# usbasp.net
KiCad netlist of a schematic drawn in EAGLE
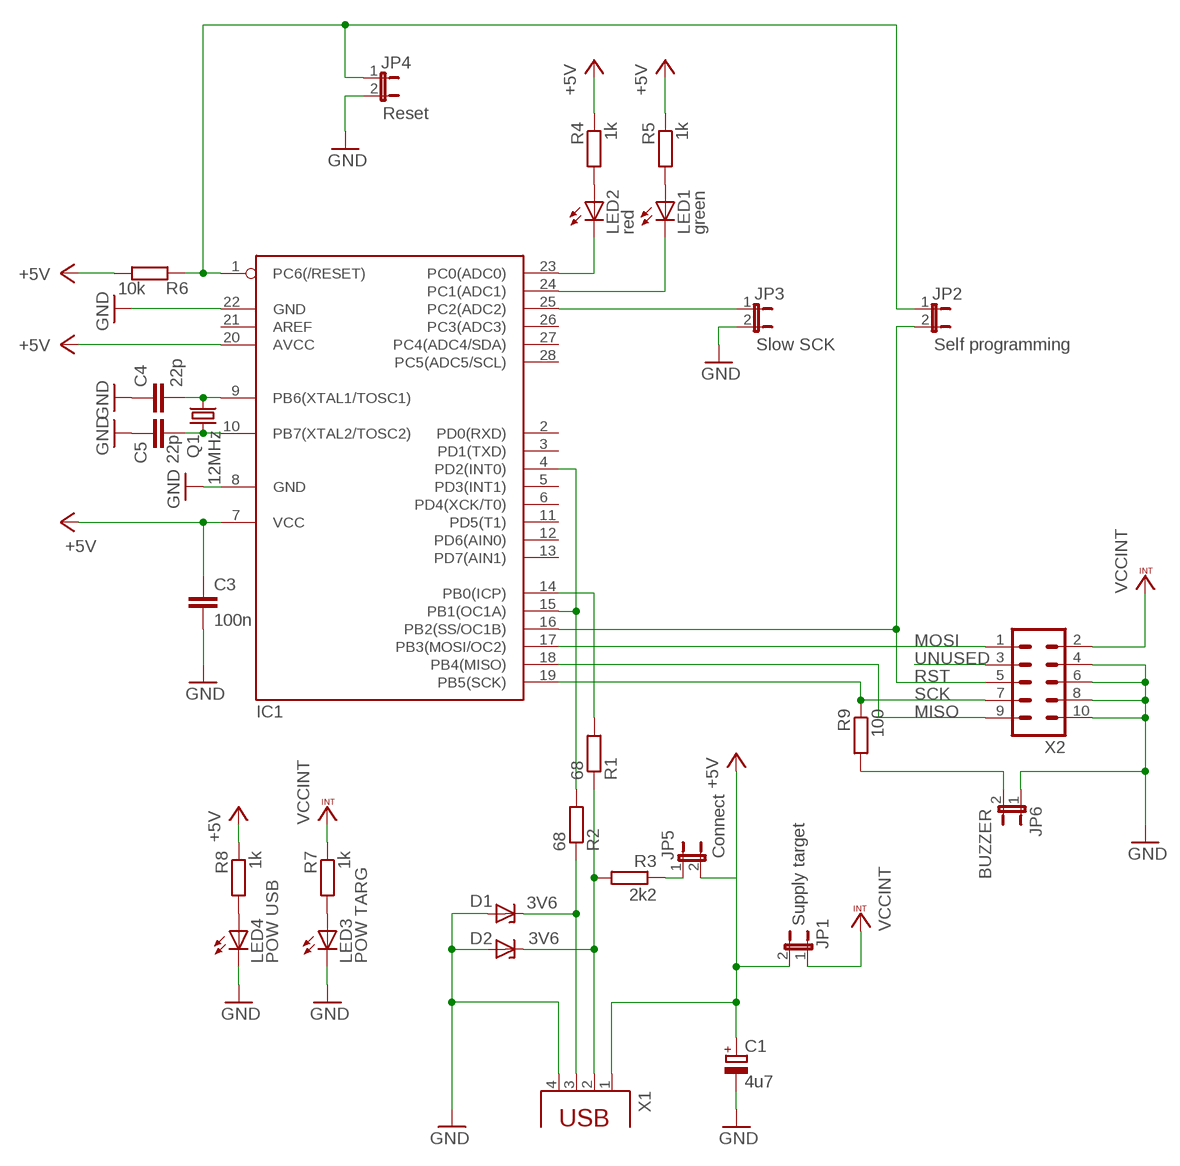
[diagram p0: schematic, sheet 1]

(export (version "E")
  (design (tool "Eeschema 10.0.6"))
  (components
    (comp (ref "C1")
      (value "4u7")
      (footprint "eagle-import:TT5D6")
      (libsource (lib "eagle-import") (part "CPOL-EUTT6D6"))
    )
    (comp (ref "C3")
      (value "100n")
      (footprint "eagle-import:C025-024X044")
      (libsource (lib "eagle-import") (part "C-EU025-024X044"))
    )
    (comp (ref "C4")
      (value "22p")
      (footprint "eagle-import:C025-024X044")
      (libsource (lib "eagle-import") (part "C-EU025-024X044"))
    )
    (comp (ref "C5")
      (value "22p")
      (footprint "eagle-import:C050-025X075")
      (libsource (lib "eagle-import") (part "C-EU050-025X075"))
    )
    (comp (ref "D1")
      (value "3V6")
      (footprint "eagle-import:DO34Z7")
      (libsource (lib "eagle-import") (part "ZENER-DIODEDO34-7"))
    )
    (comp (ref "D2")
      (value "3V6")
      (footprint "eagle-import:ZDIO-5")
      (libsource (lib "eagle-import") (part "ZENER-DIODEZD-5"))
    )
    (comp (ref "IC1")
      (value "MEGA8-P")
      (footprint "eagle-import:DIL28-3")
      (libsource (lib "eagle-import") (part "MEGA8-P"))
    )
    (comp (ref "JP1")
      (value "Supply target")
      (footprint "eagle-import:JP1")
      (libsource (lib "eagle-import") (part "JP1E"))
    )
    (comp (ref "JP2")
      (value "Self programming")
      (footprint "eagle-import:JP1")
      (libsource (lib "eagle-import") (part "JP1E"))
    )
    (comp (ref "JP3")
      (value "Slow SCK")
      (footprint "eagle-import:JP1")
      (libsource (lib "eagle-import") (part "JP1E"))
    )
    (comp (ref "JP4")
      (value "Reset")
      (footprint "eagle-import:JP1")
      (libsource (lib "eagle-import") (part "JP1E"))
    )
    (comp (ref "JP5")
      (value "Connect")
      (footprint "eagle-import:JP1")
      (libsource (lib "eagle-import") (part "JP1E"))
    )
    (comp (ref "JP6")
      (value "BUZZER")
      (footprint "eagle-import:JP1")
      (libsource (lib "eagle-import") (part "JP1E"))
    )
    (comp (ref "LED1")
      (value "green")
      (footprint "eagle-import:LED3MM")
      (libsource (lib "eagle-import") (part "LED3MM"))
    )
    (comp (ref "LED2")
      (value "red")
      (footprint "eagle-import:LED3MM")
      (libsource (lib "eagle-import") (part "LED3MM"))
    )
    (comp (ref "LED3")
      (value "POW TARG")
      (footprint "eagle-import:LED3MM")
      (libsource (lib "eagle-import") (part "LED3MM"))
    )
    (comp (ref "LED4")
      (value "POW USB")
      (footprint "eagle-import:LED3MM")
      (libsource (lib "eagle-import") (part "LED3MM"))
    )
    (comp (ref "Q1")
      (value "12MHz")
      (footprint "eagle-import:TC26V")
      (libsource (lib "eagle-import") (part "CRYSTALTC26V"))
    )
    (comp (ref "R1")
      (value "68")
      (footprint "eagle-import:R1206")
      (libsource (lib "eagle-import") (part "R-EU_R1206"))
    )
    (comp (ref "R2")
      (value "68")
      (footprint "eagle-import:0204V")
      (libsource (lib "eagle-import") (part "R-EU_0204/2V"))
    )
    (comp (ref "R3")
      (value "2k2")
      (footprint "eagle-import:0617_17")
      (libsource (lib "eagle-import") (part "R-EU_0617/17"))
    )
    (comp (ref "R4")
      (value "1k")
      (footprint "eagle-import:0204_5")
      (libsource (lib "eagle-import") (part "R-EU_0204/5"))
    )
    (comp (ref "R5")
      (value "1k")
      (footprint "eagle-import:0207_12")
      (libsource (lib "eagle-import") (part "R-EU_0207/12"))
    )
    (comp (ref "R6")
      (value "10k")
      (footprint "eagle-import:0207_15")
      (libsource (lib "eagle-import") (part "R-EU_0207/15"))
    )
    (comp (ref "R7")
      (value "1k")
      (footprint "eagle-import:0204V")
      (libsource (lib "eagle-import") (part "R-EU_0204/2V"))
    )
    (comp (ref "R8")
      (value "1k")
      (footprint "eagle-import:0204_5")
      (libsource (lib "eagle-import") (part "R-EU_0204/5"))
    )
    (comp (ref "R9")
      (value "100")
      (footprint "eagle-import:0207_15")
      (libsource (lib "eagle-import") (part "R-EU_0207/15"))
    )
    (comp (ref "X1")
      (value "PN61729")
      (footprint "eagle-import:PN61729")
      (libsource (lib "eagle-import") (part "PN61729"))
    )
    (comp (ref "X2")
      (value "ML10L")
      (footprint "eagle-import:ML10L")
      (libsource (lib "eagle-import") (part "ML10L"))
    )
  )
  (nets
    (net (code "1") (name "+5V") (class "Default")
      (node (ref "C1") (pin "+") (pinfunction "+_+") (pintype "passive"))
      (node (ref "C3") (pin "1") (pinfunction "1_1") (pintype "passive"))
      (node (ref "IC1") (pin "20") (pinfunction "AVCC_20") (pintype "power_in"))
      (node (ref "IC1") (pin "7") (pinfunction "VCC_7") (pintype "power_in"))
      (node (ref "JP1") (pin "2") (pinfunction "2_2") (pintype "passive"))
      (node (ref "JP5") (pin "2") (pinfunction "2_2") (pintype "passive"))
      (node (ref "R4") (pin "1") (pinfunction "1_1") (pintype "passive"))
      (node (ref "R5") (pin "1") (pinfunction "1_1") (pintype "passive"))
      (node (ref "R6") (pin "1") (pinfunction "1_1") (pintype "passive"))
      (node (ref "R8") (pin "1") (pinfunction "1_1") (pintype "passive"))
      (node (ref "X1") (pin "1") (pinfunction "1_1") (pintype "passive"))
    )
    (net (code "2") (name "/MISO") (class "Default")
      (node (ref "IC1") (pin "18") (pinfunction "PB4(MISO)_18") (pintype "bidirectional"))
      (node (ref "X2") (pin "9") (pinfunction "9_9") (pintype "passive"))
    )
    (net (code "3") (name "/MOSI") (class "Default")
      (node (ref "IC1") (pin "17") (pinfunction "PB3(MOSI/OC2)_17") (pintype "bidirectional"))
      (node (ref "X2") (pin "1") (pinfunction "1_1") (pintype "passive"))
    )
    (net (code "4") (name "/RST") (class "Default")
      (node (ref "IC1") (pin "16") (pinfunction "PB2(SS/OC1B)_16") (pintype "bidirectional"))
      (node (ref "JP2") (pin "2") (pinfunction "2_2") (pintype "passive"))
      (node (ref "X2") (pin "5") (pinfunction "5_5") (pintype "passive"))
    )
    (net (code "5") (name "/SCK") (class "Default")
      (node (ref "IC1") (pin "19") (pinfunction "PB5(SCK)_19") (pintype "bidirectional"))
      (node (ref "R9") (pin "1") (pinfunction "1_1") (pintype "passive"))
      (node (ref "X2") (pin "7") (pinfunction "7_7") (pintype "passive"))
    )
    (net (code "6") (name "/UNUSED") (class "Default")
      (node (ref "X2") (pin "3") (pinfunction "3_3") (pintype "passive"))
    )
    (net (code "7") (name "GND") (class "Default")
      (node (ref "C1") (pin "-") (pinfunction "-_-") (pintype "passive"))
      (node (ref "C3") (pin "2") (pinfunction "2_2") (pintype "passive"))
      (node (ref "C4") (pin "1") (pinfunction "1_1") (pintype "passive"))
      (node (ref "C5") (pin "1") (pinfunction "1_1") (pintype "passive"))
      (node (ref "D1") (pin "A") (pinfunction "A_A") (pintype "passive"))
      (node (ref "D2") (pin "A") (pinfunction "A_A") (pintype "passive"))
      (node (ref "IC1") (pin "22") (pinfunction "GND_22") (pintype "power_in"))
      (node (ref "IC1") (pin "8") (pinfunction "GND_8") (pintype "power_in"))
      (node (ref "JP3") (pin "2") (pinfunction "2_2") (pintype "passive"))
      (node (ref "JP4") (pin "2") (pinfunction "2_2") (pintype "passive"))
      (node (ref "JP6") (pin "1") (pinfunction "1_1") (pintype "passive"))
      (node (ref "LED3") (pin "K") (pinfunction "C_K") (pintype "passive"))
      (node (ref "LED4") (pin "K") (pinfunction "C_K") (pintype "passive"))
      (node (ref "X1") (pin "4") (pinfunction "4_4") (pintype "passive"))
      (node (ref "X2") (pin "10") (pinfunction "10_10") (pintype "passive"))
      (node (ref "X2") (pin "4") (pinfunction "4_4") (pintype "passive"))
      (node (ref "X2") (pin "6") (pinfunction "6_6") (pintype "passive"))
      (node (ref "X2") (pin "8") (pinfunction "8_8") (pintype "passive"))
    )
    (net (code "8") (name "Net-(D1-PadC)") (class "Default")
      (node (ref "D1") (pin "C") (pinfunction "C_C") (pintype "passive"))
      (node (ref "R2") (pin "1") (pinfunction "1_1") (pintype "passive"))
      (node (ref "X1") (pin "3") (pinfunction "3_3") (pintype "passive"))
    )
    (net (code "9") (name "Net-(D2-PadC)") (class "Default")
      (node (ref "D2") (pin "C") (pinfunction "C_C") (pintype "passive"))
      (node (ref "R1") (pin "1") (pinfunction "1_1") (pintype "passive"))
      (node (ref "R3") (pin "2") (pinfunction "2_2") (pintype "passive"))
      (node (ref "X1") (pin "2") (pinfunction "2_2") (pintype "passive"))
    )
    (net (code "10") (name "Net-(IC1-PB0(ICP))") (class "Default")
      (node (ref "IC1") (pin "14") (pinfunction "PB0(ICP)_14") (pintype "bidirectional"))
      (node (ref "R1") (pin "2") (pinfunction "2_2") (pintype "passive"))
    )
    (net (code "11") (name "Net-(IC1-PB1(OC1A))") (class "Default")
      (node (ref "IC1") (pin "15") (pinfunction "PB1(OC1A)_15") (pintype "bidirectional"))
      (node (ref "IC1") (pin "4") (pinfunction "PD2(INT0)_4") (pintype "bidirectional"))
      (node (ref "R2") (pin "2") (pinfunction "2_2") (pintype "passive"))
    )
    (net (code "12") (name "Net-(IC1-PB6(XTAL1{slash}TOSC1))") (class "Default")
      (node (ref "C4") (pin "2") (pinfunction "2_2") (pintype "passive"))
      (node (ref "IC1") (pin "9") (pinfunction "PB6(XTAL1/TOSC1)_9") (pintype "bidirectional"))
      (node (ref "Q1") (pin "2") (pinfunction "2_2") (pintype "passive"))
    )
    (net (code "13") (name "Net-(IC1-PB7(XTAL2{slash}TOSC2))") (class "Default")
      (node (ref "C5") (pin "2") (pinfunction "2_2") (pintype "passive"))
      (node (ref "IC1") (pin "10") (pinfunction "PB7(XTAL2/TOSC2)_10") (pintype "bidirectional"))
      (node (ref "Q1") (pin "1") (pinfunction "1_1") (pintype "passive"))
    )
    (net (code "14") (name "Net-(IC1-PC0(ADC0))") (class "Default")
      (node (ref "IC1") (pin "23") (pinfunction "PC0(ADC0)_23") (pintype "bidirectional"))
      (node (ref "LED2") (pin "K") (pinfunction "C_K") (pintype "passive"))
    )
    (net (code "15") (name "Net-(IC1-PC1(ADC1))") (class "Default")
      (node (ref "IC1") (pin "24") (pinfunction "PC1(ADC1)_24") (pintype "bidirectional"))
      (node (ref "LED1") (pin "K") (pinfunction "C_K") (pintype "passive"))
    )
    (net (code "16") (name "Net-(IC1-PC2(ADC2))") (class "Default")
      (node (ref "IC1") (pin "25") (pinfunction "PC2(ADC2)_25") (pintype "bidirectional"))
      (node (ref "JP3") (pin "1") (pinfunction "1_1") (pintype "passive"))
    )
    (net (code "17") (name "Net-(IC1-PC6({slash}RESET))") (class "Default")
      (node (ref "IC1") (pin "1") (pinfunction "PC6(/RESET)_1") (pintype "bidirectional"))
      (node (ref "JP2") (pin "1") (pinfunction "1_1") (pintype "passive"))
      (node (ref "JP4") (pin "1") (pinfunction "1_1") (pintype "passive"))
      (node (ref "R6") (pin "2") (pinfunction "2_2") (pintype "passive"))
    )
    (net (code "18") (name "Net-(JP5-Pad1)") (class "Default")
      (node (ref "JP5") (pin "1") (pinfunction "1_1") (pintype "passive"))
      (node (ref "R3") (pin "1") (pinfunction "1_1") (pintype "passive"))
    )
    (net (code "19") (name "Net-(JP6-Pad2)") (class "Default")
      (node (ref "JP6") (pin "2") (pinfunction "2_2") (pintype "passive"))
      (node (ref "R9") (pin "2") (pinfunction "2_2") (pintype "passive"))
    )
    (net (code "20") (name "Net-(LED1-PadA)") (class "Default")
      (node (ref "LED1") (pin "A") (pinfunction "A_A") (pintype "passive"))
      (node (ref "R5") (pin "2") (pinfunction "2_2") (pintype "passive"))
    )
    (net (code "21") (name "Net-(LED2-PadA)") (class "Default")
      (node (ref "LED2") (pin "A") (pinfunction "A_A") (pintype "passive"))
      (node (ref "R4") (pin "2") (pinfunction "2_2") (pintype "passive"))
    )
    (net (code "22") (name "Net-(LED3-PadA)") (class "Default")
      (node (ref "LED3") (pin "A") (pinfunction "A_A") (pintype "passive"))
      (node (ref "R7") (pin "2") (pinfunction "2_2") (pintype "passive"))
    )
    (net (code "23") (name "Net-(LED4-PadA)") (class "Default")
      (node (ref "LED4") (pin "A") (pinfunction "A_A") (pintype "passive"))
      (node (ref "R8") (pin "2") (pinfunction "2_2") (pintype "passive"))
    )
    (net (code "24") (name "VCCINT") (class "Default")
      (node (ref "JP1") (pin "1") (pinfunction "1_1") (pintype "passive"))
      (node (ref "R7") (pin "1") (pinfunction "1_1") (pintype "passive"))
      (node (ref "X2") (pin "2") (pinfunction "2_2") (pintype "passive"))
    )
    (net (code "25") (name "unconnected-(IC1-AREF-Pad21)") (class "Default")
      (node (ref "IC1") (pin "21") (pinfunction "AREF_21") (pintype "passive"))
    )
    (net (code "26") (name "unconnected-(IC1-PC3(ADC3)-Pad26)") (class "Default")
      (node (ref "IC1") (pin "26") (pinfunction "PC3(ADC3)_26") (pintype "bidirectional"))
    )
    (net (code "27") (name "unconnected-(IC1-PC4(ADC4{slash}SDA)-Pad27)") (class "Default")
      (node (ref "IC1") (pin "27") (pinfunction "PC4(ADC4/SDA)_27") (pintype "bidirectional"))
    )
    (net (code "28") (name "unconnected-(IC1-PC5(ADC5{slash}SCL)-Pad28)") (class "Default")
      (node (ref "IC1") (pin "28") (pinfunction "PC5(ADC5/SCL)_28") (pintype "bidirectional"))
    )
    (net (code "29") (name "unconnected-(IC1-PD0(RXD)-Pad2)") (class "Default")
      (node (ref "IC1") (pin "2") (pinfunction "PD0(RXD)_2") (pintype "bidirectional"))
    )
    (net (code "30") (name "unconnected-(IC1-PD1(TXD)-Pad3)") (class "Default")
      (node (ref "IC1") (pin "3") (pinfunction "PD1(TXD)_3") (pintype "bidirectional"))
    )
    (net (code "31") (name "unconnected-(IC1-PD3(INT1)-Pad5)") (class "Default")
      (node (ref "IC1") (pin "5") (pinfunction "PD3(INT1)_5") (pintype "bidirectional"))
    )
    (net (code "32") (name "unconnected-(IC1-PD4(XCK{slash}T0)-Pad6)") (class "Default")
      (node (ref "IC1") (pin "6") (pinfunction "PD4(XCK/T0)_6") (pintype "bidirectional"))
    )
    (net (code "33") (name "unconnected-(IC1-PD5(T1)-Pad11)") (class "Default")
      (node (ref "IC1") (pin "11") (pinfunction "PD5(T1)_11") (pintype "bidirectional"))
    )
    (net (code "34") (name "unconnected-(IC1-PD6(AIN0)-Pad12)") (class "Default")
      (node (ref "IC1") (pin "12") (pinfunction "PD6(AIN0)_12") (pintype "bidirectional"))
    )
    (net (code "35") (name "unconnected-(IC1-PD7(AIN1)-Pad13)") (class "Default")
      (node (ref "IC1") (pin "13") (pinfunction "PD7(AIN1)_13") (pintype "bidirectional"))
    )
  )
)
